# emonDC_Buck_Module_v0_1.net
KiCad netlist of a schematic drawn in EAGLE
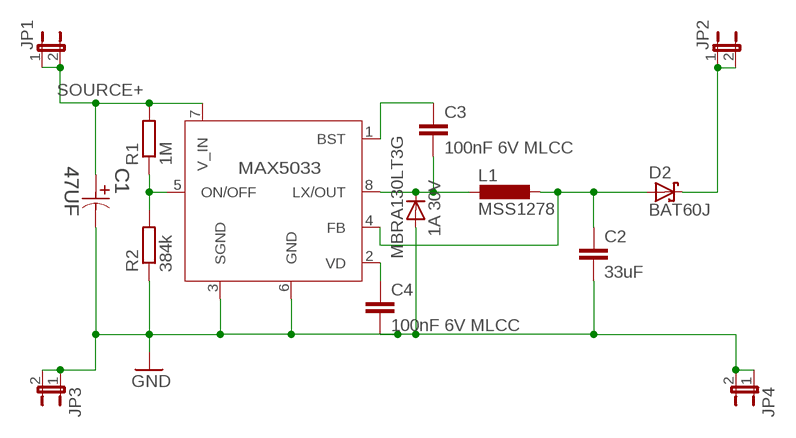
[diagram p0: schematic, sheet 1]

(export (version "E")
  (design (tool "Eeschema 10.0.6"))
  (components
    (comp (ref "C1")
      (value "47UF")
      (footprint "eagle-import:CAPAE1350X1400N")
      (fields (field (name "MPN") "EEVFK2A470Q") (field (name "TOLERANCE") "±20 %"))
      (libsource (lib "eagle-import") (part "EEV--CASE-H13FK2A470Q"))
    )
    (comp (ref "C2")
      (value "33uF")
      (footprint "eagle-import:C1210")
      (fields (field (name "MPN") "TCQB336M006R0070"))
      (libsource (lib "eagle-import") (part "rcl_334_C-EUC1210"))
    )
    (comp (ref "C3")
      (value "100nF 6V MLCC")
      (footprint "eagle-import:C0603")
      (libsource (lib "eagle-import") (part "C-EUC0603"))
    )
    (comp (ref "C4")
      (value "100nF 6V MLCC")
      (footprint "eagle-import:C0603")
      (libsource (lib "eagle-import") (part "C-EUC0603"))
    )
    (comp (ref "D1")
      (value "MBRA130LT3G")
      (footprint "eagle-import:DO-214")
      (fields (field (name "MF") "ON SEMICONDUCTOR"))
      (libsource (lib "eagle-import") (part "MBRA130LT3G"))
    )
    (comp (ref "D2")
      (value "BAT60J")
      (footprint "eagle-import:SOD323_ST")
      (libsource (lib "eagle-import") (part "BAT60J"))
    )
    (comp (ref "JP1")
      (value "JP1E")
      (footprint "eagle-import:JP1")
      (libsource (lib "eagle-import") (part "JP1E"))
    )
    (comp (ref "JP2")
      (value "JP1E")
      (footprint "eagle-import:JP1")
      (libsource (lib "eagle-import") (part "JP1E"))
    )
    (comp (ref "JP3")
      (value "JP1E")
      (footprint "eagle-import:JP1")
      (libsource (lib "eagle-import") (part "JP1E"))
    )
    (comp (ref "JP4")
      (value "JP1E")
      (footprint "eagle-import:JP1")
      (libsource (lib "eagle-import") (part "JP1E"))
    )
    (comp (ref "L1")
      (value "MSS1278")
      (footprint "eagle-import:MSS1278")
      (fields (field (name "MPN") "MSS1278-224KLD"))
      (libsource (lib "eagle-import") (part "MSS1278"))
    )
    (comp (ref "MAX5033")
      (value "MAX5033BUSA+")
      (footprint "eagle-import:21-0111D_SBE-14")
      (libsource (lib "eagle-import") (part "MAX5033BUSA+"))
    )
    (comp (ref "R1")
      (value "1M")
      (footprint "eagle-import:R0603")
      (libsource (lib "eagle-import") (part "R-EU_R0603"))
    )
    (comp (ref "R2")
      (value "384k")
      (footprint "eagle-import:R0603")
      (libsource (lib "eagle-import") (part "R-EU_R0603"))
    )
  )
  (nets
    (net (code "1") (name "/SOURCE+") (class "Default")
      (node (ref "C1") (pin "1") (pinfunction "1_1") (pintype "passive"))
      (node (ref "JP1") (pin "1") (pinfunction "1_1") (pintype "passive"))
      (node (ref "JP1") (pin "2") (pinfunction "2_2") (pintype "passive"))
      (node (ref "MAX5033") (pin "7") (pinfunction "V_IN_7") (pintype "power_in"))
      (node (ref "R1") (pin "2") (pinfunction "2_2") (pintype "passive"))
    )
    (net (code "2") (name "GND") (class "Default")
      (node (ref "C1") (pin "2") (pinfunction "2_2") (pintype "passive"))
      (node (ref "C2") (pin "2") (pinfunction "2_2") (pintype "passive"))
      (node (ref "C4") (pin "2") (pinfunction "2_2") (pintype "passive"))
      (node (ref "D1") (pin "P$2") (pinfunction "A_P$2") (pintype "passive"))
      (node (ref "JP3") (pin "1") (pinfunction "1_1") (pintype "passive"))
      (node (ref "JP3") (pin "2") (pinfunction "2_2") (pintype "passive"))
      (node (ref "JP4") (pin "1") (pinfunction "1_1") (pintype "passive"))
      (node (ref "JP4") (pin "2") (pinfunction "2_2") (pintype "passive"))
      (node (ref "MAX5033") (pin "3") (pinfunction "SGND_3") (pintype "power_in"))
      (node (ref "MAX5033") (pin "6") (pinfunction "GND_6") (pintype "passive"))
      (node (ref "R2") (pin "1") (pinfunction "1_1") (pintype "passive"))
    )
    (net (code "3") (name "Net-(D1-C)") (class "Default")
      (node (ref "C3") (pin "2") (pinfunction "2_2") (pintype "passive"))
      (node (ref "D1") (pin "P$1") (pinfunction "C_P$1") (pintype "passive"))
      (node (ref "L1") (pin "P$2") (pinfunction "2_P$2") (pintype "passive"))
      (node (ref "MAX5033") (pin "8") (pinfunction "LX/OUT_8") (pintype "output"))
    )
    (net (code "4") (name "Net-(D2-PadC)") (class "Default")
      (node (ref "D2") (pin "C") (pinfunction "C_C") (pintype "passive"))
      (node (ref "JP2") (pin "1") (pinfunction "1_1") (pintype "passive"))
      (node (ref "JP2") (pin "2") (pinfunction "2_2") (pintype "passive"))
    )
    (net (code "5") (name "Net-(L1-1)") (class "Default")
      (node (ref "C2") (pin "1") (pinfunction "1_1") (pintype "passive"))
      (node (ref "D2") (pin "A") (pinfunction "A_A") (pintype "passive"))
      (node (ref "L1") (pin "P$1") (pinfunction "1_P$1") (pintype "passive"))
      (node (ref "MAX5033") (pin "4") (pinfunction "FB_4") (pintype "input"))
    )
    (net (code "6") (name "Net-(MAX5033-BST)") (class "Default")
      (node (ref "C3") (pin "1") (pinfunction "1_1") (pintype "passive"))
      (node (ref "MAX5033") (pin "1") (pinfunction "BST_1") (pintype "passive"))
    )
    (net (code "7") (name "Net-(MAX5033-ON{slash}OFF)") (class "Default")
      (node (ref "MAX5033") (pin "5") (pinfunction "ON/OFF_5") (pintype "input"))
      (node (ref "R1") (pin "1") (pinfunction "1_1") (pintype "passive"))
      (node (ref "R2") (pin "2") (pinfunction "2_2") (pintype "passive"))
    )
    (net (code "8") (name "Net-(MAX5033-VD)") (class "Default")
      (node (ref "C4") (pin "1") (pinfunction "1_1") (pintype "passive"))
      (node (ref "MAX5033") (pin "2") (pinfunction "VD_2") (pintype "input"))
    )
  )
)
